# mux-optical.net
KiCad netlist of a schematic drawn in Altium Designer
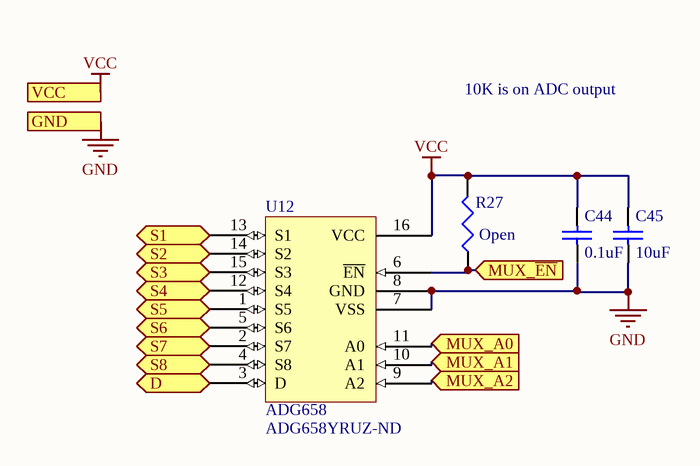
[diagram p0: mux-optical.SchDoc]

(export (version "E")
  (design (tool "Eeschema 10.0.6"))
  (components
    (comp (ref "C44")
      (value "0.1uF")
      (footprint "0402")
      (description "Capacitor (Semiconductor SIM Model)")
      (fields (field (name "PUBLISHER") "Altium Limited"))
      (libsource (lib "Miscellaneous Devices") (part "Cap Semi"))
    )
    (comp (ref "C45")
      (value "10uF")
      (footprint "1608[0603]")
      (description "Capacitor (Semiconductor SIM Model)")
      (fields (field (name "PUBLISHER") "Altium Limited"))
      (libsource (lib "Miscellaneous Devices") (part "Cap Semi"))
    )
    (comp (ref "R27")
      (value "Open")
      (footprint "0402")
      (description "Resistor")
      (fields (field (name "PUBLISHER") "Altium Limited"))
      (libsource (lib "Miscellaneous Devices") (part "Res3"))
    )
    (comp (ref "U12")
      (value "ADG658")
      (footprint "SSOP16_N")
      (description "Eight channel analog multiplexer.")
      (fields (field (name "SUPPLIER PART NUMBER 1") "ADG658YRUZ-ND"))
      (libsource (lib "PAY") (part "ADG658"))
    )
  )
  (nets
    (net (code "1") (name "/D") (class "Default")
      (node (ref "U12") (pin "3") (pinfunction "D_3") (pintype "bidirectional"))
    )
    (net (code "2") (name "/MUX_A0") (class "Default")
      (node (ref "U12") (pin "11") (pinfunction "A0_11") (pintype "input"))
    )
    (net (code "3") (name "/MUX_A1") (class "Default")
      (node (ref "U12") (pin "10") (pinfunction "A1_10") (pintype "input"))
    )
    (net (code "4") (name "/MUX_A2") (class "Default")
      (node (ref "U12") (pin "9") (pinfunction "A2_9") (pintype "input"))
    )
    (net (code "5") (name "/MUX_~{EN}") (class "Default")
      (node (ref "R27") (pin "1") (pinfunction "1_1") (pintype "passive"))
      (node (ref "U12") (pin "6") (pinfunction "~{EN}_6") (pintype "input"))
    )
    (net (code "6") (name "/S1") (class "Default")
      (node (ref "U12") (pin "13") (pinfunction "S1_13") (pintype "bidirectional"))
    )
    (net (code "7") (name "/S2") (class "Default")
      (node (ref "U12") (pin "14") (pinfunction "S2_14") (pintype "bidirectional"))
    )
    (net (code "8") (name "/S3") (class "Default")
      (node (ref "U12") (pin "15") (pinfunction "S3_15") (pintype "bidirectional"))
    )
    (net (code "9") (name "/S4") (class "Default")
      (node (ref "U12") (pin "12") (pinfunction "S4_12") (pintype "bidirectional"))
    )
    (net (code "10") (name "/S5") (class "Default")
      (node (ref "U12") (pin "1") (pinfunction "S5_1") (pintype "bidirectional"))
    )
    (net (code "11") (name "/S6") (class "Default")
      (node (ref "U12") (pin "5") (pinfunction "S6_5") (pintype "bidirectional"))
    )
    (net (code "12") (name "/S7") (class "Default")
      (node (ref "U12") (pin "2") (pinfunction "S7_2") (pintype "bidirectional"))
    )
    (net (code "13") (name "/S8") (class "Default")
      (node (ref "U12") (pin "4") (pinfunction "S8_4") (pintype "bidirectional"))
    )
    (net (code "14") (name "GND") (class "Default")
      (node (ref "C44") (pin "1") (pinfunction "1_1") (pintype "passive"))
      (node (ref "C45") (pin "1") (pinfunction "1_1") (pintype "passive"))
      (node (ref "U12") (pin "7") (pinfunction "VSS_7") (pintype "power_in"))
      (node (ref "U12") (pin "8") (pinfunction "GND_8") (pintype "power_in"))
    )
    (net (code "15") (name "VCC") (class "Default")
      (node (ref "C44") (pin "2") (pinfunction "2_2") (pintype "passive"))
      (node (ref "C45") (pin "2") (pinfunction "2_2") (pintype "passive"))
      (node (ref "R27") (pin "2") (pinfunction "2_2") (pintype "passive"))
      (node (ref "U12") (pin "16") (pinfunction "VCC_16") (pintype "power_in"))
    )
  )
)
